# ETRX_Shield.net
KiCad netlist of a schematic drawn in Altium Designer
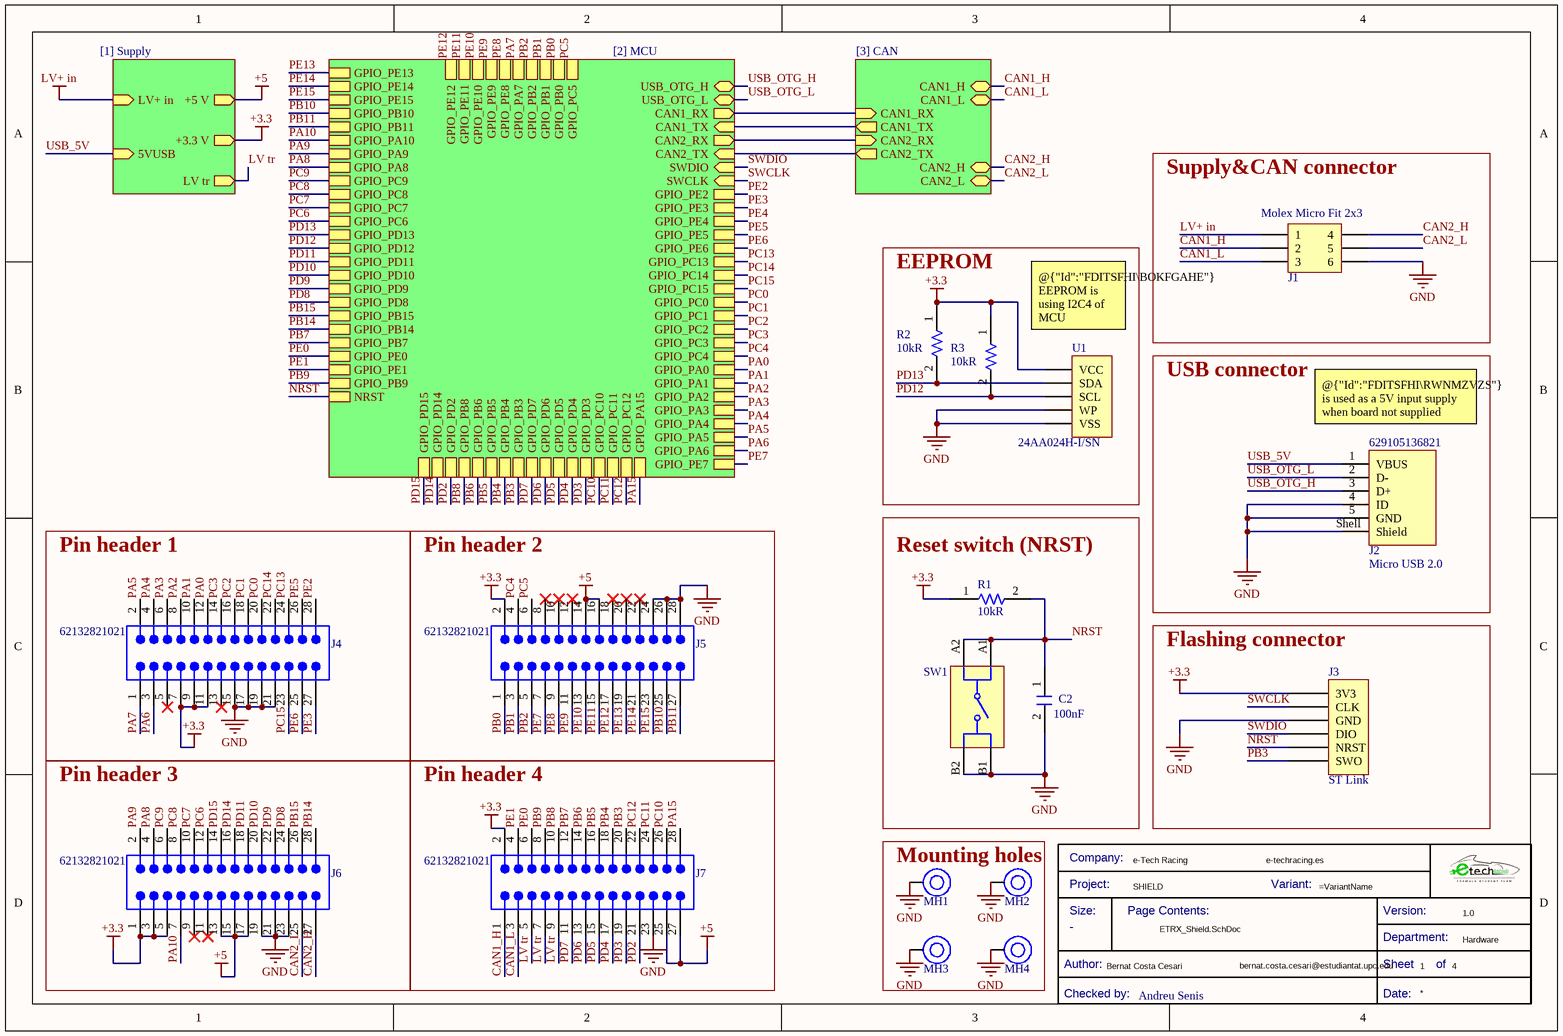
[diagram p0: ETRX_Shield.SchDoc]

(export (version "E")
  (design (tool "Eeschema 10.0.6"))
  (components
    (comp (ref "*")
      (value "Title Block_template")
      (description "Standard Title Block")
      (fields
        (field (name "SIZE") "-")
        (field (name ".CREATOR") "GP")
        (field (name ".PCBCHECK") "GP")
        (field (name ".SCHCHECK") "GP")
      )
      (libsource (lib "e-Tech_Racing") (part "Title Block_template"))
    )
    (comp (ref "C2")
      (value "885012207098")
      (footprint "C0805FNPC-R")
      (description "Cap, 0.1ΜF, 50V, 10%, X7R, 0805")
      (fields
        (field (name "TOLERANCE") "10%")
        (field (name "CAPACITANCE") "100nF")
        (field (name ".CREATOR") "DR")
      )
      (libsource (lib "Passives") (part "C100n-50V-0805FNPC-X7R"))
    )
    (comp (ref "J1")
      (value "Molex Micro Fit 2x3")
      (footprint "J_MicroFit_2x3_V")
      (description "Micro fit Header, 2 Row, Vertical, Polarizing Peg, 6 Pin, Tin Plate, SMT/Glow Wire, Kinked Leads")
      (fields
        (field (name "MANUFACTURER") "Molex")
        (field (name "MANUFACTURER PART NUMBER") "43045-0612")
        (field (name ".CREATOR") "DO")
      )
      (libsource (lib "Electromechanical") (part "J_MicroFit_2x3_V"))
    )
    (comp (ref "J2")
      (value "629105136821")
      (footprint "629105136821")
      (description "WR-COM Micro USB 2.0 SMT Type B Horizontal 5 Contacts")
      (fields (field (name "MANUFACTURER") "Wurth Elektronik"))
      (libsource (lib "WR-USB") (part "629105136821"))
    )
    (comp (ref "J3")
      (value "ST Link")
      (footprint "J_STLink_PinHeader")
      (libsource (lib "Electromechanical") (part "J_STLink_STM32_PinHeader_1x6"))
    )
    (comp (ref "J4")
      (value "62132821021")
      (footprint "62132821021")
      (description "WR-PHD Pin Header, SMT, Vertical, pitch 1.27mm, 2 Row, 28P")
      (fields (field (name "MANUFACTURER") "Wurth Elektronik"))
      (libsource (lib "Electromechanical") (part "62132821021"))
    )
    (comp (ref "J5")
      (value "62132821021")
      (footprint "62132821021")
      (description "WR-PHD Pin Header, SMT, Vertical, pitch 1.27mm, 2 Row, 28P")
      (fields (field (name "MANUFACTURER") "Wurth Elektronik"))
      (libsource (lib "Electromechanical") (part "62132821021"))
    )
    (comp (ref "J6")
      (value "62132821021")
      (footprint "62132821021")
      (description "WR-PHD Pin Header, SMT, Vertical, pitch 1.27mm, 2 Row, 28P")
      (fields (field (name "MANUFACTURER") "Wurth Elektronik"))
      (libsource (lib "Electromechanical") (part "62132821021"))
    )
    (comp (ref "J7")
      (value "62132821021")
      (footprint "62132821021")
      (description "WR-PHD Pin Header, SMT, Vertical, pitch 1.27mm, 2 Row, 28P")
      (fields (field (name "MANUFACTURER") "Wurth Elektronik"))
      (libsource (lib "Electromechanical") (part "62132821021"))
    )
    (comp (ref "MH1")
      (value "Mounting_Hole_M3")
      (footprint "Mounting_Hole_M3")
      (libsource (lib "Electromechanical") (part "Mounting_Hole_M3"))
    )
    (comp (ref "MH2")
      (value "Mounting_Hole_M3")
      (footprint "Mounting_Hole_M3")
      (libsource (lib "Electromechanical") (part "Mounting_Hole_M3"))
    )
    (comp (ref "MH3")
      (value "Mounting_Hole_M3")
      (footprint "Mounting_Hole_M3")
      (libsource (lib "Electromechanical") (part "Mounting_Hole_M3"))
    )
    (comp (ref "MH4")
      (value "Mounting_Hole_M3")
      (footprint "Mounting_Hole_M3")
      (libsource (lib "Electromechanical") (part "Mounting_Hole_M3"))
    )
    (comp (ref "R1")
      (value "CR0805-JW-103ELF")
      (footprint "R0805FTK")
      (fields
        (field (name "TOLERANCE") "5%")
        (field (name "RESISTANCE") "10kR")
        (field (name ".CREATOR") "DR")
      )
      (libsource (lib "Passives") (part "R10k-0805FTK"))
    )
    (comp (ref "R2")
      (value "CR0805-JW-103ELF")
      (footprint "R0805FTK")
      (fields
        (field (name "TOLERANCE") "5%")
        (field (name "RESISTANCE") "10kR")
        (field (name ".CREATOR") "DR")
      )
      (libsource (lib "Passives") (part "R10k-0805FTK"))
    )
    (comp (ref "R3")
      (value "CR0805-JW-103ELF")
      (footprint "R0805FTK")
      (fields
        (field (name "TOLERANCE") "5%")
        (field (name "RESISTANCE") "10kR")
        (field (name ".CREATOR") "DR")
      )
      (libsource (lib "Passives") (part "R10k-0805FTK"))
    )
    (comp (ref "SW1")
      (value "430773034825")
      (footprint "WS-TASV_L6W6H3.4_4307x30348xx")
      (description "WS-TASV J-Hook SMT Hermetic Tact Switch, L6 x W6 x H3.4mm, 250g, SPST-NO, 12V, 50mA")
      (fields (field (name "MANUFACTURER") "Wurth Elektronik"))
      (libsource (lib "Altium_WS-SW bo") (part "430773034825"))
    )
    (comp (ref "U1")
      (value "24AA024H-I/SN")
      (footprint "SOIC, 8-Leads 1,27mm")
      (description "24AA02\r\n2Kb I2C compatible 2-wire Serial EEPROM")
      (libsource (lib "Integrated circuits") (part "EEPROM 24AA02I2C 2K Microchip"))
    )
  )
  (nets
    (net (code "1") (name "+3.3") (class "Default")
      (node (ref "J3") (pin "1") (pinfunction "3V3_1") (pintype "passive"))
      (node (ref "J4") (pin "11") (pinfunction "11_11") (pintype "passive"))
      (node (ref "J4") (pin "7") (pinfunction "7_7") (pintype "passive"))
      (node (ref "J4") (pin "9") (pinfunction "9_9") (pintype "passive"))
      (node (ref "J5") (pin "2") (pinfunction "2_2") (pintype "passive"))
      (node (ref "J6") (pin "1") (pinfunction "1_1") (pintype "passive"))
      (node (ref "J6") (pin "3") (pinfunction "3_3") (pintype "passive"))
      (node (ref "J6") (pin "5") (pinfunction "5_5") (pintype "passive"))
      (node (ref "J7") (pin "2") (pinfunction "2_2") (pintype "passive"))
      (node (ref "R1") (pin "1") (pinfunction "1_1") (pintype "passive"))
      (node (ref "R2") (pin "1") (pinfunction "1_1") (pintype "passive"))
      (node (ref "R3") (pin "1") (pinfunction "1_1") (pintype "passive"))
      (node (ref "U1") (pin "8") (pinfunction "VCC_8") (pintype "passive"))
    )
    (net (code "2") (name "+5") (class "Default")
      (node (ref "J5") (pin "14") (pinfunction "14_14") (pintype "passive"))
      (node (ref "J5") (pin "16") (pinfunction "16_16") (pintype "passive"))
      (node (ref "J6") (pin "13") (pinfunction "13_13") (pintype "passive"))
      (node (ref "J6") (pin "15") (pinfunction "15_15") (pintype "passive"))
      (node (ref "J6") (pin "17") (pinfunction "17_17") (pintype "passive"))
      (node (ref "J7") (pin "25") (pinfunction "25_25") (pintype "passive"))
      (node (ref "J7") (pin "27") (pinfunction "27_27") (pintype "passive"))
    )
    (net (code "3") (name "/CAN1_H") (class "Default")
      (node (ref "J1") (pin "2") (pinfunction "2_2") (pintype "passive"))
      (node (ref "J7") (pin "1") (pinfunction "1_1") (pintype "passive"))
    )
    (net (code "4") (name "/CAN1_L") (class "Default")
      (node (ref "J1") (pin "3") (pinfunction "3_3") (pintype "passive"))
      (node (ref "J7") (pin "3") (pinfunction "3_3") (pintype "passive"))
    )
    (net (code "7") (name "/CAN2_H") (class "Default")
      (node (ref "J1") (pin "4") (pinfunction "4_4") (pintype "passive"))
      (node (ref "J6") (pin "27") (pinfunction "27_27") (pintype "passive"))
    )
    (net (code "8") (name "/CAN2_L") (class "Default")
      (node (ref "J1") (pin "5") (pinfunction "5_5") (pintype "passive"))
      (node (ref "J6") (pin "25") (pinfunction "25_25") (pintype "passive"))
    )
    (net (code "11") (name "/LV tr") (class "Default")
      (node (ref "J7") (pin "5") (pinfunction "5_5") (pintype "passive"))
      (node (ref "J7") (pin "7") (pinfunction "7_7") (pintype "passive"))
      (node (ref "J7") (pin "9") (pinfunction "9_9") (pintype "passive"))
    )
    (net (code "12") (name "/NRST") (class "Default")
      (node (ref "C2") (pin "1") (pinfunction "1_1") (pintype "passive"))
      (node (ref "J3") (pin "5") (pinfunction "NRST_5") (pintype "passive"))
      (node (ref "R1") (pin "2") (pinfunction "2_2") (pintype "passive"))
      (node (ref "SW1") (pin "A1") (pinfunction "A1_A1") (pintype "passive"))
      (node (ref "SW1") (pin "A2") (pinfunction "A2_A2") (pintype "passive"))
    )
    (net (code "13") (name "/PA0") (class "Default")
      (node (ref "J4") (pin "12") (pinfunction "12_12") (pintype "passive"))
    )
    (net (code "14") (name "/PA1") (class "Default")
      (node (ref "J4") (pin "10") (pinfunction "10_10") (pintype "passive"))
    )
    (net (code "15") (name "/PA2") (class "Default")
      (node (ref "J4") (pin "8") (pinfunction "8_8") (pintype "passive"))
    )
    (net (code "16") (name "/PA3") (class "Default")
      (node (ref "J4") (pin "6") (pinfunction "6_6") (pintype "passive"))
    )
    (net (code "17") (name "/PA4") (class "Default")
      (node (ref "J4") (pin "4") (pinfunction "4_4") (pintype "passive"))
    )
    (net (code "18") (name "/PA5") (class "Default")
      (node (ref "J4") (pin "2") (pinfunction "2_2") (pintype "passive"))
    )
    (net (code "19") (name "/PA6") (class "Default")
      (node (ref "J4") (pin "3") (pinfunction "3_3") (pintype "passive"))
    )
    (net (code "20") (name "/PA7") (class "Default")
      (node (ref "J4") (pin "1") (pinfunction "1_1") (pintype "passive"))
    )
    (net (code "21") (name "/PA8") (class "Default")
      (node (ref "J6") (pin "4") (pinfunction "4_4") (pintype "passive"))
    )
    (net (code "22") (name "/PA9") (class "Default")
      (node (ref "J6") (pin "2") (pinfunction "2_2") (pintype "passive"))
    )
    (net (code "23") (name "/PA10") (class "Default")
      (node (ref "J6") (pin "7") (pinfunction "7_7") (pintype "passive"))
    )
    (net (code "24") (name "/PA15") (class "Default")
      (node (ref "J7") (pin "28") (pinfunction "28_28") (pintype "passive"))
    )
    (net (code "25") (name "/PB0") (class "Default")
      (node (ref "J5") (pin "1") (pinfunction "1_1") (pintype "passive"))
    )
    (net (code "26") (name "/PB1") (class "Default")
      (node (ref "J5") (pin "3") (pinfunction "3_3") (pintype "passive"))
    )
    (net (code "27") (name "/PB2") (class "Default")
      (node (ref "J5") (pin "5") (pinfunction "5_5") (pintype "passive"))
    )
    (net (code "28") (name "/PB3") (class "Default")
      (node (ref "J3") (pin "6") (pinfunction "SWO_6") (pintype "passive"))
      (node (ref "J7") (pin "20") (pinfunction "20_20") (pintype "passive"))
    )
    (net (code "29") (name "/PB4") (class "Default")
      (node (ref "J7") (pin "18") (pinfunction "18_18") (pintype "passive"))
    )
    (net (code "30") (name "/PB5") (class "Default")
      (node (ref "J7") (pin "16") (pinfunction "16_16") (pintype "passive"))
    )
    (net (code "31") (name "/PB6") (class "Default")
      (node (ref "J7") (pin "14") (pinfunction "14_14") (pintype "passive"))
    )
    (net (code "32") (name "/PB7") (class "Default")
      (node (ref "J7") (pin "12") (pinfunction "12_12") (pintype "passive"))
    )
    (net (code "33") (name "/PB8") (class "Default")
      (node (ref "J7") (pin "10") (pinfunction "10_10") (pintype "passive"))
    )
    (net (code "34") (name "/PB9") (class "Default")
      (node (ref "J7") (pin "8") (pinfunction "8_8") (pintype "passive"))
    )
    (net (code "35") (name "/PB10") (class "Default")
      (node (ref "J5") (pin "25") (pinfunction "25_25") (pintype "passive"))
    )
    (net (code "36") (name "/PB11") (class "Default")
      (node (ref "J5") (pin "27") (pinfunction "27_27") (pintype "passive"))
    )
    (net (code "37") (name "/PB14") (class "Default")
      (node (ref "J6") (pin "28") (pinfunction "28_28") (pintype "passive"))
    )
    (net (code "38") (name "/PB15") (class "Default")
      (node (ref "J6") (pin "26") (pinfunction "26_26") (pintype "passive"))
    )
    (net (code "39") (name "/PC0") (class "Default")
      (node (ref "J4") (pin "20") (pinfunction "20_20") (pintype "passive"))
    )
    (net (code "40") (name "/PC1") (class "Default")
      (node (ref "J4") (pin "18") (pinfunction "18_18") (pintype "passive"))
    )
    (net (code "41") (name "/PC2") (class "Default")
      (node (ref "J4") (pin "16") (pinfunction "16_16") (pintype "passive"))
    )
    (net (code "42") (name "/PC3") (class "Default")
      (node (ref "J4") (pin "14") (pinfunction "14_14") (pintype "passive"))
    )
    (net (code "43") (name "/PC4") (class "Default")
      (node (ref "J5") (pin "4") (pinfunction "4_4") (pintype "passive"))
    )
    (net (code "44") (name "/PC5") (class "Default")
      (node (ref "J5") (pin "6") (pinfunction "6_6") (pintype "passive"))
    )
    (net (code "45") (name "/PC6") (class "Default")
      (node (ref "J6") (pin "12") (pinfunction "12_12") (pintype "passive"))
    )
    (net (code "46") (name "/PC7") (class "Default")
      (node (ref "J6") (pin "10") (pinfunction "10_10") (pintype "passive"))
    )
    (net (code "47") (name "/PC8") (class "Default")
      (node (ref "J6") (pin "8") (pinfunction "8_8") (pintype "passive"))
    )
    (net (code "48") (name "/PC9") (class "Default")
      (node (ref "J6") (pin "6") (pinfunction "6_6") (pintype "passive"))
    )
    (net (code "49") (name "/PC10") (class "Default")
      (node (ref "J7") (pin "26") (pinfunction "26_26") (pintype "passive"))
    )
    (net (code "50") (name "/PC11") (class "Default")
      (node (ref "J7") (pin "24") (pinfunction "24_24") (pintype "passive"))
    )
    (net (code "51") (name "/PC12") (class "Default")
      (node (ref "J7") (pin "22") (pinfunction "22_22") (pintype "passive"))
    )
    (net (code "52") (name "/PC13") (class "Default")
      (node (ref "J4") (pin "24") (pinfunction "24_24") (pintype "passive"))
    )
    (net (code "53") (name "/PC14") (class "Default")
      (node (ref "J4") (pin "22") (pinfunction "22_22") (pintype "passive"))
    )
    (net (code "54") (name "/PC15") (class "Default")
      (node (ref "J4") (pin "23") (pinfunction "23_23") (pintype "passive"))
    )
    (net (code "55") (name "/PD2") (class "Default")
      (node (ref "J7") (pin "21") (pinfunction "21_21") (pintype "passive"))
    )
    (net (code "56") (name "/PD3") (class "Default")
      (node (ref "J7") (pin "19") (pinfunction "19_19") (pintype "passive"))
    )
    (net (code "57") (name "/PD4") (class "Default")
      (node (ref "J7") (pin "17") (pinfunction "17_17") (pintype "passive"))
    )
    (net (code "58") (name "/PD5") (class "Default")
      (node (ref "J7") (pin "15") (pinfunction "15_15") (pintype "passive"))
    )
    (net (code "59") (name "/PD6") (class "Default")
      (node (ref "J7") (pin "13") (pinfunction "13_13") (pintype "passive"))
    )
    (net (code "60") (name "/PD7") (class "Default")
      (node (ref "J7") (pin "11") (pinfunction "11_11") (pintype "passive"))
    )
    (net (code "61") (name "/PD8") (class "Default")
      (node (ref "J6") (pin "24") (pinfunction "24_24") (pintype "passive"))
    )
    (net (code "62") (name "/PD9") (class "Default")
      (node (ref "J6") (pin "22") (pinfunction "22_22") (pintype "passive"))
    )
    (net (code "63") (name "/PD10") (class "Default")
      (node (ref "J6") (pin "20") (pinfunction "20_20") (pintype "passive"))
    )
    (net (code "64") (name "/PD11") (class "Default")
      (node (ref "J6") (pin "18") (pinfunction "18_18") (pintype "passive"))
    )
    (net (code "65") (name "/PD12") (class "Default")
      (node (ref "R3") (pin "2") (pinfunction "2_2") (pintype "passive"))
      (node (ref "U1") (pin "6") (pinfunction "SCL_6") (pintype "passive"))
    )
    (net (code "66") (name "/PD13") (class "Default")
      (node (ref "R2") (pin "2") (pinfunction "2_2") (pintype "passive"))
      (node (ref "U1") (pin "5") (pinfunction "SDA_5") (pintype "passive"))
    )
    (net (code "67") (name "/PD14") (class "Default")
      (node (ref "J6") (pin "16") (pinfunction "16_16") (pintype "passive"))
    )
    (net (code "68") (name "/PD15") (class "Default")
      (node (ref "J6") (pin "14") (pinfunction "14_14") (pintype "passive"))
    )
    (net (code "69") (name "/PE0") (class "Default")
      (node (ref "J7") (pin "6") (pinfunction "6_6") (pintype "passive"))
    )
    (net (code "70") (name "/PE1") (class "Default")
      (node (ref "J7") (pin "4") (pinfunction "4_4") (pintype "passive"))
    )
    (net (code "71") (name "/PE2") (class "Default")
      (node (ref "J4") (pin "28") (pinfunction "28_28") (pintype "passive"))
    )
    (net (code "72") (name "/PE3") (class "Default")
      (node (ref "J4") (pin "27") (pinfunction "27_27") (pintype "passive"))
    )
    (net (code "74") (name "/PE5") (class "Default")
      (node (ref "J4") (pin "26") (pinfunction "26_26") (pintype "passive"))
    )
    (net (code "75") (name "/PE6") (class "Default")
      (node (ref "J4") (pin "25") (pinfunction "25_25") (pintype "passive"))
    )
    (net (code "76") (name "/PE7") (class "Default")
      (node (ref "J5") (pin "7") (pinfunction "7_7") (pintype "passive"))
    )
    (net (code "77") (name "/PE8") (class "Default")
      (node (ref "J5") (pin "9") (pinfunction "9_9") (pintype "passive"))
    )
    (net (code "78") (name "/PE9") (class "Default")
      (node (ref "J5") (pin "11") (pinfunction "11_11") (pintype "passive"))
    )
    (net (code "79") (name "/PE10") (class "Default")
      (node (ref "J5") (pin "13") (pinfunction "13_13") (pintype "passive"))
    )
    (net (code "80") (name "/PE11") (class "Default")
      (node (ref "J5") (pin "15") (pinfunction "15_15") (pintype "passive"))
    )
    (net (code "81") (name "/PE12") (class "Default")
      (node (ref "J5") (pin "17") (pinfunction "17_17") (pintype "passive"))
    )
    (net (code "82") (name "/PE13") (class "Default")
      (node (ref "J5") (pin "19") (pinfunction "19_19") (pintype "passive"))
    )
    (net (code "83") (name "/PE14") (class "Default")
      (node (ref "J5") (pin "21") (pinfunction "21_21") (pintype "passive"))
    )
    (net (code "84") (name "/PE15") (class "Default")
      (node (ref "J5") (pin "23") (pinfunction "23_23") (pintype "passive"))
    )
    (net (code "85") (name "/SWCLK") (class "Default")
      (node (ref "J3") (pin "2") (pinfunction "CLK_2") (pintype "passive"))
    )
    (net (code "86") (name "/SWDIO") (class "Default")
      (node (ref "J3") (pin "4") (pinfunction "DIO_4") (pintype "passive"))
    )
    (net (code "87") (name "/USB_5V") (class "Default")
      (node (ref "J2") (pin "1") (pinfunction "VBUS_1") (pintype "passive"))
    )
    (net (code "88") (name "/USB_OTG_H") (class "Default")
      (node (ref "J2") (pin "3") (pinfunction "D+_3") (pintype "passive"))
    )
    (net (code "89") (name "/USB_OTG_L") (class "Default")
      (node (ref "J2") (pin "2") (pinfunction "D-_2") (pintype "passive"))
    )
    (net (code "90") (name "GND") (class "Default")
      (node (ref "C2") (pin "2") (pinfunction "2_2") (pintype "passive"))
      (node (ref "J1") (pin "6") (pinfunction "6_6") (pintype "passive"))
      (node (ref "J2") (pin "4") (pinfunction "ID_4") (pintype "passive"))
      (node (ref "J2") (pin "5") (pinfunction "GND_5") (pintype "passive"))
      (node (ref "J2") (pin "Shell") (pinfunction "Shield_Shell") (pintype "passive"))
      (node (ref "J3") (pin "3") (pinfunction "GND_3") (pintype "passive"))
      (node (ref "J4") (pin "15") (pinfunction "15_15") (pintype "passive"))
      (node (ref "J4") (pin "17") (pinfunction "17_17") (pintype "passive"))
      (node (ref "J4") (pin "19") (pinfunction "19_19") (pintype "passive"))
      (node (ref "J4") (pin "21") (pinfunction "21_21") (pintype "passive"))
      (node (ref "J5") (pin "24") (pinfunction "24_24") (pintype "passive"))
      (node (ref "J5") (pin "26") (pinfunction "26_26") (pintype "passive"))
      (node (ref "J5") (pin "28") (pinfunction "28_28") (pintype "passive"))
      (node (ref "J6") (pin "19") (pinfunction "19_19") (pintype "passive"))
      (node (ref "J6") (pin "21") (pinfunction "21_21") (pintype "passive"))
      (node (ref "J6") (pin "23") (pinfunction "23_23") (pintype "passive"))
      (node (ref "J7") (pin "23") (pinfunction "23_23") (pintype "passive"))
      (node (ref "MH1") (pin "1") (pinfunction "1_1") (pintype "passive"))
      (node (ref "MH2") (pin "1") (pinfunction "1_1") (pintype "passive"))
      (node (ref "MH3") (pin "1") (pinfunction "1_1") (pintype "passive"))
      (node (ref "MH4") (pin "1") (pinfunction "1_1") (pintype "passive"))
      (node (ref "SW1") (pin "B1") (pinfunction "B1_B1") (pintype "passive"))
      (node (ref "SW1") (pin "B2") (pinfunction "B2_B2") (pintype "passive"))
      (node (ref "U1") (pin "4") (pinfunction "VSS_4") (pintype "passive"))
      (node (ref "U1") (pin "7") (pinfunction "WP_7") (pintype "passive"))
    )
    (net (code "91") (name "LV+ in") (class "Default")
      (node (ref "J1") (pin "1") (pinfunction "1_1") (pintype "passive"))
    )
    (net (code "92") (name "unconnected-(J4-Pad5)") (class "Default")
      (node (ref "J4") (pin "5") (pinfunction "5_5") (pintype "passive+no_connect"))
    )
    (net (code "93") (name "unconnected-(J4-Pad13)") (class "Default")
      (node (ref "J4") (pin "13") (pinfunction "13_13") (pintype "passive+no_connect"))
    )
    (net (code "94") (name "unconnected-(J5-Pad8)") (class "Default")
      (node (ref "J5") (pin "8") (pinfunction "8_8") (pintype "passive+no_connect"))
    )
    (net (code "95") (name "unconnected-(J5-Pad10)") (class "Default")
      (node (ref "J5") (pin "10") (pinfunction "10_10") (pintype "passive+no_connect"))
    )
    (net (code "96") (name "unconnected-(J5-Pad12)") (class "Default")
      (node (ref "J5") (pin "12") (pinfunction "12_12") (pintype "passive+no_connect"))
    )
    (net (code "97") (name "unconnected-(J5-Pad18)") (class "Default")
      (node (ref "J5") (pin "18") (pinfunction "18_18") (pintype "passive+no_connect"))
    )
    (net (code "98") (name "unconnected-(J5-Pad20)") (class "Default")
      (node (ref "J5") (pin "20") (pinfunction "20_20") (pintype "passive+no_connect"))
    )
    (net (code "99") (name "unconnected-(J5-Pad22)") (class "Default")
      (node (ref "J5") (pin "22") (pinfunction "22_22") (pintype "passive+no_connect"))
    )
    (net (code "100") (name "unconnected-(J6-Pad9)") (class "Default")
      (node (ref "J6") (pin "9") (pinfunction "9_9") (pintype "passive+no_connect"))
    )
    (net (code "101") (name "unconnected-(J6-Pad11)") (class "Default")
      (node (ref "J6") (pin "11") (pinfunction "11_11") (pintype "passive+no_connect"))
    )
  )
)
